# vfd_logic.net
KiCad netlist of a schematic drawn in EAGLE
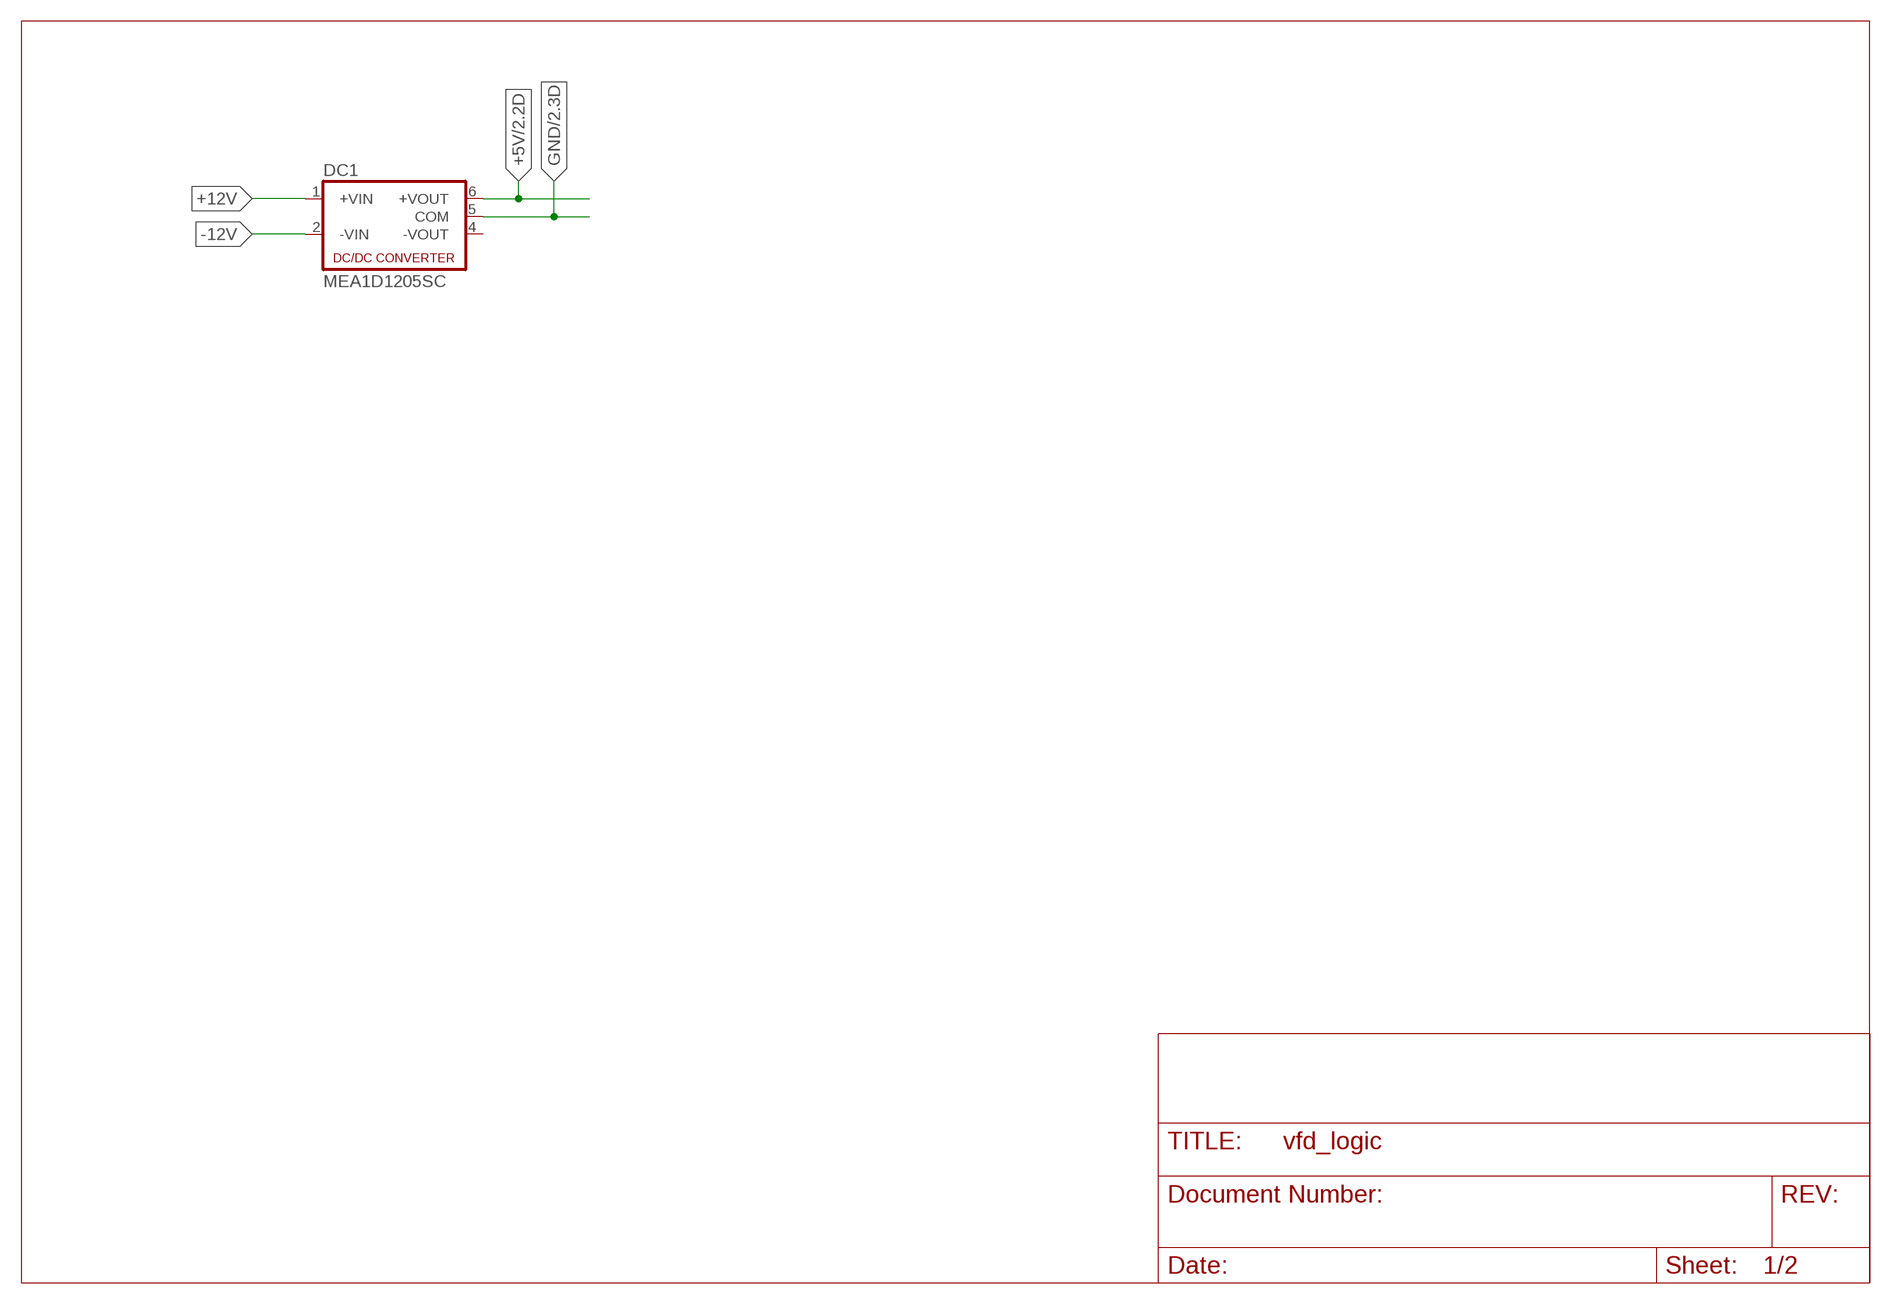
[diagram p0: schematic, sheet 1]
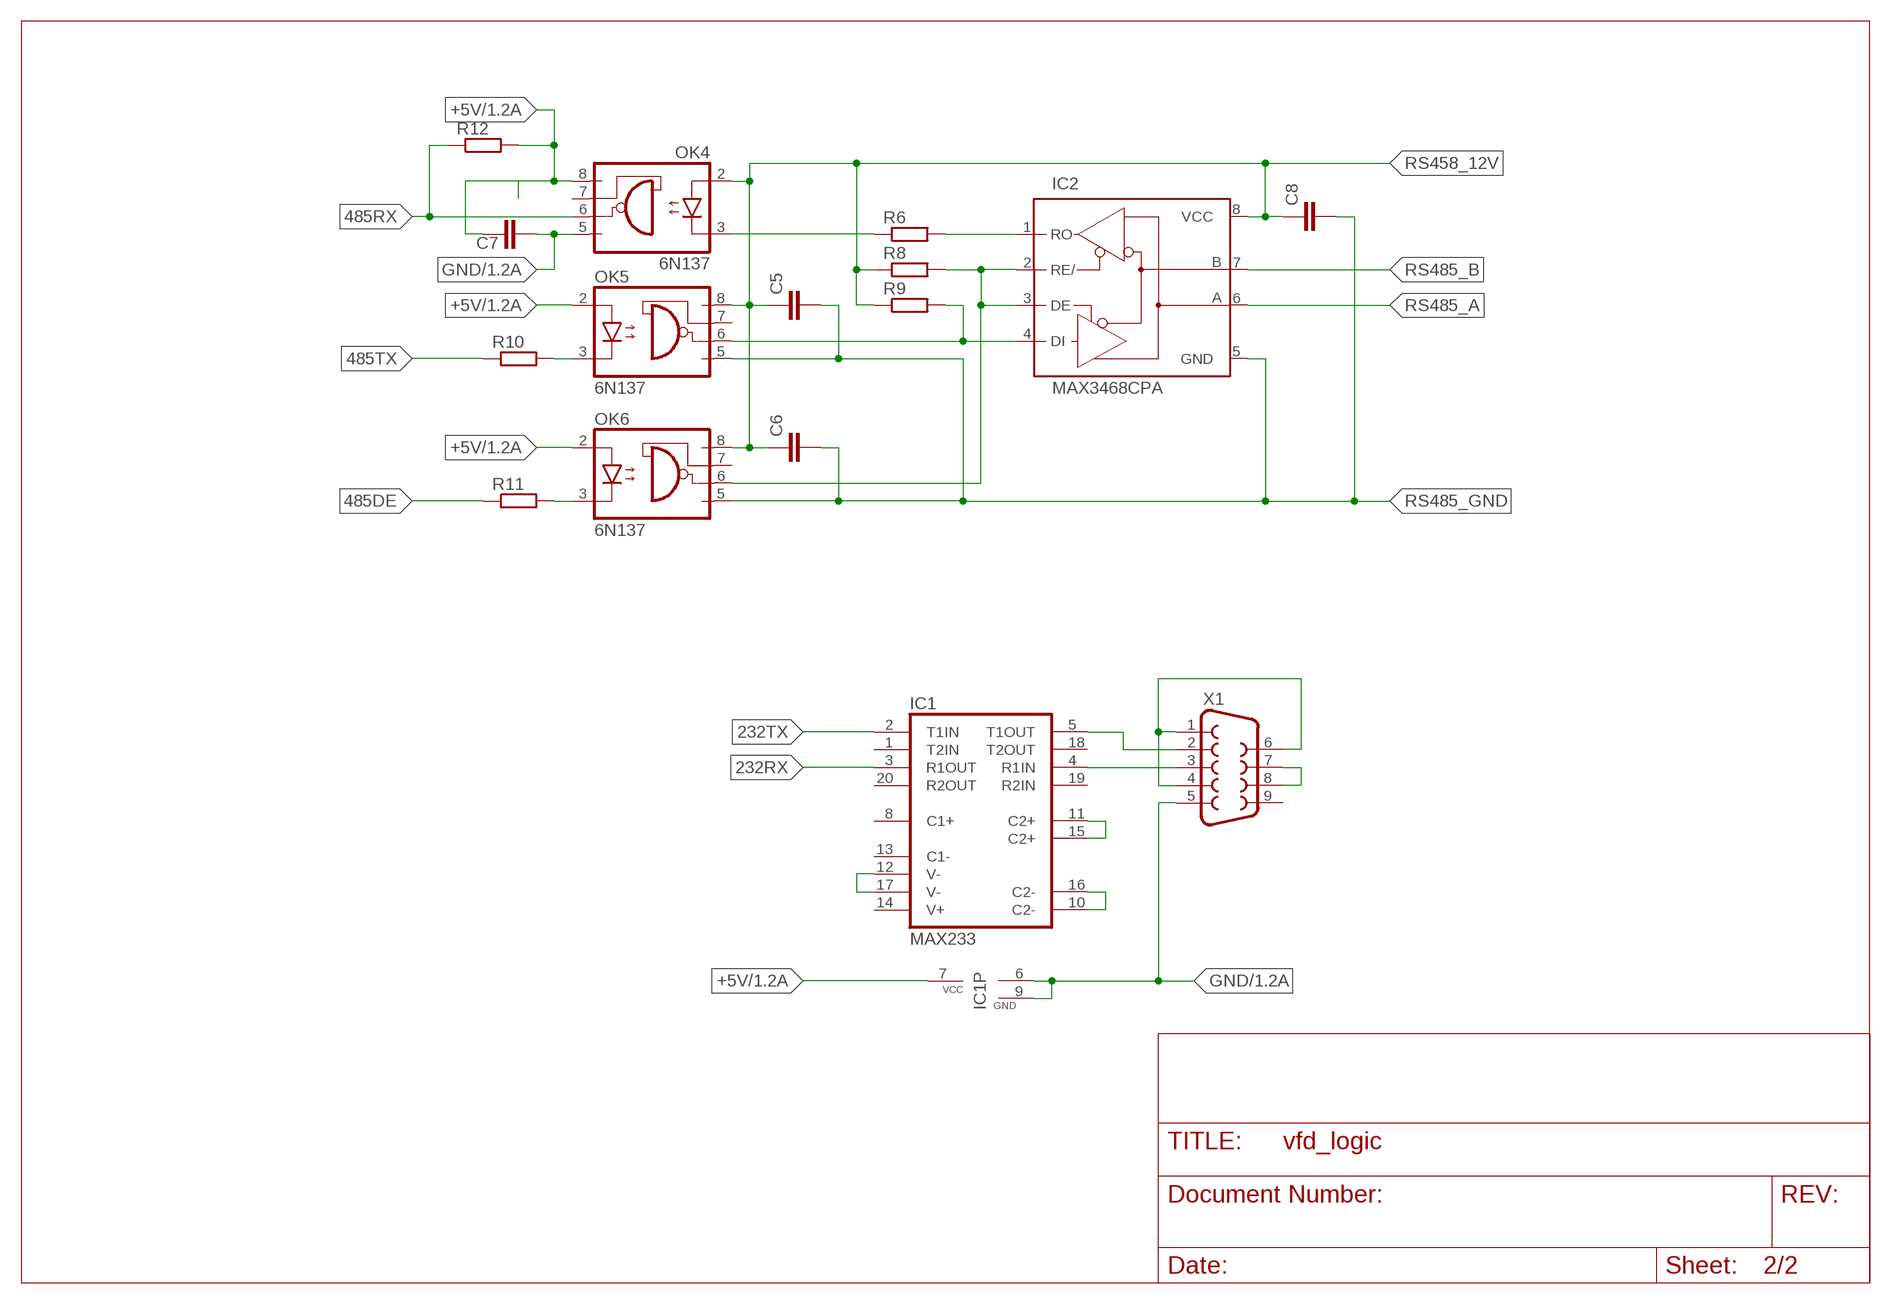
[diagram p1: schematic, sheet 2]

(export (version "E")
  (design (tool "Eeschema 10.0.6"))
  (components
    (comp (ref "DC1")
      (value "MEA1D1205SC")
      (footprint "eagle-import:NMA")
      (fields (field (name "MF") "C & D TECHNOLOGIES, INC") (field (name "MPN") "NMA0515SC"))
      (libsource (lib "eagle-import") (part "NMA"))
    )
    (comp (ref "C5")
      (value "C-EU050-030X075")
      (footprint "eagle-import:C050-030X075")
      (libsource (lib "eagle-import") (part "C-EU050-030X075"))
    )
    (comp (ref "C6")
      (value "C-EU050-030X075")
      (footprint "eagle-import:C050-030X075")
      (libsource (lib "eagle-import") (part "C-EU050-030X075"))
    )
    (comp (ref "C7")
      (value "C-EU050-030X075")
      (footprint "eagle-import:C050-030X075")
      (libsource (lib "eagle-import") (part "C-EU050-030X075"))
    )
    (comp (ref "C8")
      (value "C-EU050-030X075")
      (footprint "eagle-import:C050-030X075")
      (libsource (lib "eagle-import") (part "C-EU050-030X075"))
    )
    (comp (ref "IC1")
      (value "MAX233")
      (footprint "eagle-import:DIL20")
      (fields (field (name "MPN") "MAX233ACPP+G36"))
      (libsource (lib "eagle-import") (part "MAX233"))
    )
    (comp (ref "IC2")
      (value "MAX3468CPA")
      (footprint "eagle-import:DIL08")
      (libsource (lib "eagle-import") (part "MAX34PA68C"))
    )
    (comp (ref "OK4")
      (value "6N137")
      (footprint "eagle-import:DIL08")
      (libsource (lib "eagle-import") (part "6N137"))
    )
    (comp (ref "OK5")
      (value "6N137")
      (footprint "eagle-import:DIL08")
      (libsource (lib "eagle-import") (part "6N137"))
    )
    (comp (ref "OK6")
      (value "6N137")
      (footprint "eagle-import:DIL08")
      (libsource (lib "eagle-import") (part "6N137"))
    )
    (comp (ref "R6")
      (value "R-EU_0204/5")
      (footprint "eagle-import:0204_5")
      (libsource (lib "eagle-import") (part "R-EU_0204/5"))
    )
    (comp (ref "R8")
      (value "R-EU_0204/5")
      (footprint "eagle-import:0204_5")
      (libsource (lib "eagle-import") (part "R-EU_0204/5"))
    )
    (comp (ref "R9")
      (value "R-EU_0204/5")
      (footprint "eagle-import:0204_5")
      (libsource (lib "eagle-import") (part "R-EU_0204/5"))
    )
    (comp (ref "R10")
      (value "R-EU_0204/5")
      (footprint "eagle-import:0204_5")
      (libsource (lib "eagle-import") (part "R-EU_0204/5"))
    )
    (comp (ref "R11")
      (value "R-EU_0204/5")
      (footprint "eagle-import:0204_5")
      (libsource (lib "eagle-import") (part "R-EU_0204/5"))
    )
    (comp (ref "R12")
      (value "R-EU_0204/5")
      (footprint "eagle-import:0204_5")
      (libsource (lib "eagle-import") (part "R-EU_0204/5"))
    )
    (comp (ref "X1")
      (value "F09HP")
      (footprint "eagle-import:F09HP")
      (libsource (lib "eagle-import") (part "F09HP"))
    )
  )
  (nets
    (net (code "1") (name "+5V") (class "Default")
      (node (ref "C7") (pin "1") (pinfunction "1_1") (pintype "passive"))
      (node (ref "DC1") (pin "6") (pinfunction "+VOUT_6") (pintype "passive"))
      (node (ref "IC1") (pin "7") (pinfunction "VCC_7") (pintype "power_in"))
      (node (ref "OK4") (pin "8") (pinfunction "VCC_8") (pintype "passive"))
      (node (ref "OK5") (pin "2") (pinfunction "A_2") (pintype "passive"))
      (node (ref "OK6") (pin "2") (pinfunction "A_2") (pintype "passive"))
      (node (ref "R12") (pin "2") (pinfunction "2_2") (pintype "passive"))
    )
    (net (code "2") (name "+12V") (class "Default")
      (node (ref "DC1") (pin "1") (pinfunction "+VIN_1") (pintype "passive"))
    )
    (net (code "3") (name "-12V") (class "Default")
      (node (ref "DC1") (pin "2") (pinfunction "-VIN_2") (pintype "passive"))
    )
    (net (code "4") (name "232RX") (class "Default")
      (node (ref "IC1") (pin "3") (pinfunction "R1OUT_3") (pintype "output"))
    )
    (net (code "5") (name "232TX") (class "Default")
      (node (ref "IC1") (pin "2") (pinfunction "T1IN_2") (pintype "input"))
    )
    (net (code "6") (name "485DE") (class "Default")
      (node (ref "R11") (pin "1") (pinfunction "1_1") (pintype "passive"))
    )
    (net (code "7") (name "485RX") (class "Default")
      (node (ref "OK4") (pin "6") (pinfunction "VO_6") (pintype "passive"))
      (node (ref "R12") (pin "1") (pinfunction "1_1") (pintype "passive"))
    )
    (net (code "8") (name "485TX") (class "Default")
      (node (ref "R10") (pin "1") (pinfunction "1_1") (pintype "passive"))
    )
    (net (code "9") (name "GND") (class "Default")
      (node (ref "C7") (pin "2") (pinfunction "2_2") (pintype "passive"))
      (node (ref "DC1") (pin "5") (pinfunction "COM_5") (pintype "passive"))
      (node (ref "IC1") (pin "6") (pinfunction "GND_6") (pintype "power_in"))
      (node (ref "IC1") (pin "9") (pinfunction "GND_9") (pintype "power_in"))
      (node (ref "OK4") (pin "5") (pinfunction "GND_5") (pintype "passive"))
      (node (ref "X1") (pin "5") (pinfunction "5_5") (pintype "passive"))
    )
    (net (code "10") (name "Net-(IC1A-C2+-Pad11)") (class "Default")
      (node (ref "IC1") (pin "11") (pinfunction "C2+_11") (pintype "bidirectional"))
      (node (ref "IC1") (pin "15") (pinfunction "C2+_15") (pintype "bidirectional"))
    )
    (net (code "11") (name "Net-(IC1A-C2--Pad10)") (class "Default")
      (node (ref "IC1") (pin "10") (pinfunction "C2-_10") (pintype "bidirectional"))
      (node (ref "IC1") (pin "16") (pinfunction "C2-_16") (pintype "bidirectional"))
    )
    (net (code "12") (name "Net-(IC1A-R1IN)") (class "Default")
      (node (ref "IC1") (pin "4") (pinfunction "R1IN_4") (pintype "input"))
      (node (ref "X1") (pin "3") (pinfunction "3_3") (pintype "passive"))
    )
    (net (code "13") (name "Net-(IC1A-T1OUT)") (class "Default")
      (node (ref "IC1") (pin "5") (pinfunction "T1OUT_5") (pintype "output"))
      (node (ref "X1") (pin "2") (pinfunction "2_2") (pintype "passive"))
    )
    (net (code "14") (name "Net-(IC1A-V--Pad12)") (class "Default")
      (node (ref "IC1") (pin "12") (pinfunction "V-_12") (pintype "bidirectional"))
      (node (ref "IC1") (pin "17") (pinfunction "V-_17") (pintype "bidirectional"))
    )
    (net (code "15") (name "Net-(IC2-DE)") (class "Default")
      (node (ref "IC2") (pin "2") (pinfunction "RE/_2") (pintype "input"))
      (node (ref "IC2") (pin "3") (pinfunction "DE_3") (pintype "input"))
      (node (ref "OK6") (pin "6") (pinfunction "VO_6") (pintype "passive"))
      (node (ref "R8") (pin "2") (pinfunction "2_2") (pintype "passive"))
    )
    (net (code "16") (name "Net-(IC2-DI)") (class "Default")
      (node (ref "IC2") (pin "4") (pinfunction "DI_4") (pintype "input"))
      (node (ref "OK5") (pin "6") (pinfunction "VO_6") (pintype "passive"))
      (node (ref "R9") (pin "2") (pinfunction "2_2") (pintype "passive"))
    )
    (net (code "17") (name "Net-(IC2-RO)") (class "Default")
      (node (ref "IC2") (pin "1") (pinfunction "RO_1") (pintype "output"))
      (node (ref "R6") (pin "2") (pinfunction "2_2") (pintype "passive"))
    )
    (net (code "18") (name "Net-(OK4-C)") (class "Default")
      (node (ref "OK4") (pin "3") (pinfunction "C_3") (pintype "passive"))
      (node (ref "R6") (pin "1") (pinfunction "1_1") (pintype "passive"))
    )
    (net (code "19") (name "Net-(OK5-C)") (class "Default")
      (node (ref "OK5") (pin "3") (pinfunction "C_3") (pintype "passive"))
      (node (ref "R10") (pin "2") (pinfunction "2_2") (pintype "passive"))
    )
    (net (code "20") (name "Net-(OK6-C)") (class "Default")
      (node (ref "OK6") (pin "3") (pinfunction "C_3") (pintype "passive"))
      (node (ref "R11") (pin "2") (pinfunction "2_2") (pintype "passive"))
    )
    (net (code "21") (name "Net-(X1-Pad1)") (class "Default")
      (node (ref "X1") (pin "1") (pinfunction "1_1") (pintype "passive"))
      (node (ref "X1") (pin "4") (pinfunction "4_4") (pintype "passive"))
      (node (ref "X1") (pin "6") (pinfunction "6_6") (pintype "passive"))
    )
    (net (code "22") (name "Net-(X1-Pad7)") (class "Default")
      (node (ref "X1") (pin "7") (pinfunction "7_7") (pintype "passive"))
      (node (ref "X1") (pin "8") (pinfunction "8_8") (pintype "passive"))
    )
    (net (code "23") (name "RS458_12V") (class "Default")
      (node (ref "C5") (pin "1") (pinfunction "1_1") (pintype "passive"))
      (node (ref "C6") (pin "1") (pinfunction "1_1") (pintype "passive"))
      (node (ref "C8") (pin "1") (pinfunction "1_1") (pintype "passive"))
      (node (ref "IC2") (pin "8") (pinfunction "VCC_8") (pintype "power_in"))
      (node (ref "OK4") (pin "2") (pinfunction "A_2") (pintype "passive"))
      (node (ref "OK5") (pin "8") (pinfunction "VCC_8") (pintype "passive"))
      (node (ref "OK6") (pin "8") (pinfunction "VCC_8") (pintype "passive"))
      (node (ref "R8") (pin "1") (pinfunction "1_1") (pintype "passive"))
      (node (ref "R9") (pin "1") (pinfunction "1_1") (pintype "passive"))
    )
    (net (code "24") (name "RS485_A") (class "Default")
      (node (ref "IC2") (pin "6") (pinfunction "A_6") (pintype "passive"))
    )
    (net (code "25") (name "RS485_B") (class "Default")
      (node (ref "IC2") (pin "7") (pinfunction "B_7") (pintype "passive"))
    )
    (net (code "26") (name "RS485_GND") (class "Default")
      (node (ref "C5") (pin "2") (pinfunction "2_2") (pintype "passive"))
      (node (ref "C6") (pin "2") (pinfunction "2_2") (pintype "passive"))
      (node (ref "C8") (pin "2") (pinfunction "2_2") (pintype "passive"))
      (node (ref "IC2") (pin "5") (pinfunction "GND_5") (pintype "power_in"))
      (node (ref "OK5") (pin "5") (pinfunction "GND_5") (pintype "passive"))
      (node (ref "OK6") (pin "5") (pinfunction "GND_5") (pintype "passive"))
    )
    (net (code "27") (name "unconnected-(DC1--VOUT-Pad4)") (class "Default")
      (node (ref "DC1") (pin "4") (pinfunction "-VOUT_4") (pintype "passive"))
    )
    (net (code "28") (name "unconnected-(IC1A-C1+-Pad8)") (class "Default")
      (node (ref "IC1") (pin "8") (pinfunction "C1+_8") (pintype "bidirectional"))
    )
    (net (code "29") (name "unconnected-(IC1A-C1--Pad13)") (class "Default")
      (node (ref "IC1") (pin "13") (pinfunction "C1-_13") (pintype "bidirectional"))
    )
    (net (code "30") (name "unconnected-(IC1A-R2IN-Pad19)") (class "Default")
      (node (ref "IC1") (pin "19") (pinfunction "R2IN_19") (pintype "input"))
    )
    (net (code "31") (name "unconnected-(IC1A-R2OUT-Pad20)") (class "Default")
      (node (ref "IC1") (pin "20") (pinfunction "R2OUT_20") (pintype "output"))
    )
    (net (code "32") (name "unconnected-(IC1A-T2IN-Pad1)") (class "Default")
      (node (ref "IC1") (pin "1") (pinfunction "T2IN_1") (pintype "input"))
    )
    (net (code "33") (name "unconnected-(IC1A-T2OUT-Pad18)") (class "Default")
      (node (ref "IC1") (pin "18") (pinfunction "T2OUT_18") (pintype "output"))
    )
    (net (code "34") (name "unconnected-(IC1A-V+-Pad14)") (class "Default")
      (node (ref "IC1") (pin "14") (pinfunction "V+_14") (pintype "bidirectional"))
    )
    (net (code "35") (name "unconnected-(OK4-VE-Pad7)") (class "Default")
      (node (ref "OK4") (pin "7") (pinfunction "VE_7") (pintype "passive"))
    )
    (net (code "36") (name "unconnected-(OK5-VE-Pad7)") (class "Default")
      (node (ref "OK5") (pin "7") (pinfunction "VE_7") (pintype "passive"))
    )
    (net (code "37") (name "unconnected-(OK6-VE-Pad7)") (class "Default")
      (node (ref "OK6") (pin "7") (pinfunction "VE_7") (pintype "passive"))
    )
    (net (code "38") (name "unconnected-(X1-Pad9)") (class "Default")
      (node (ref "X1") (pin "9") (pinfunction "9_9") (pintype "passive"))
    )
  )
)
